# ConnectorHead_RPi.net
KiCad netlist of a schematic drawn in EAGLE
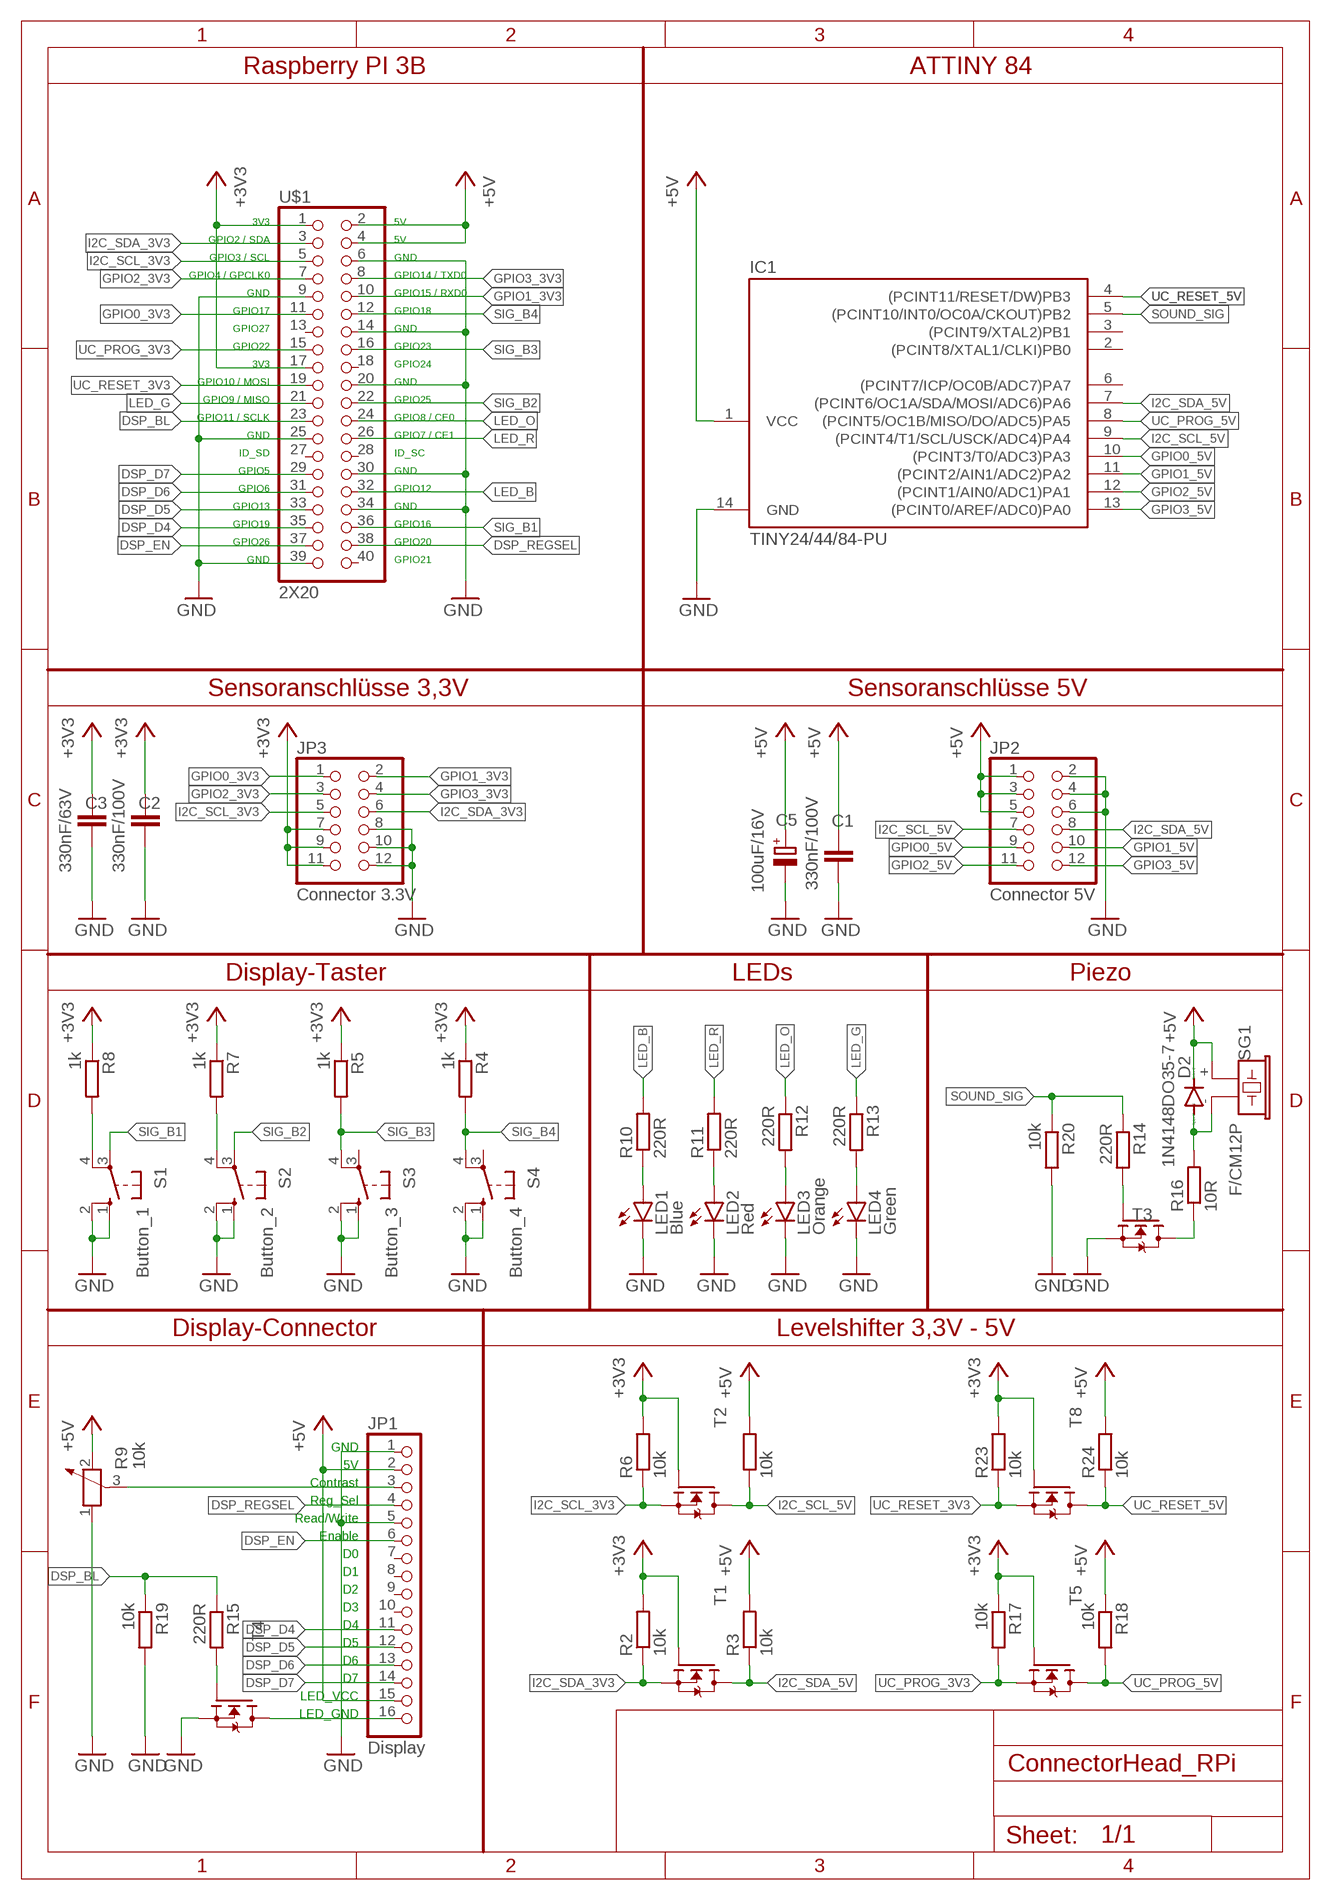
[diagram p0: schematic, sheet 1]

(export (version "E")
  (design (tool "Eeschema 10.0.6"))
  (components
    (comp (ref "C1")
      (value "330nF/100V")
      (footprint "eagle-import:C075-042X103")
      (libsource (lib "eagle-import") (part "C-EU075-042X103"))
    )
    (comp (ref "C2")
      (value "330nF/100V")
      (footprint "eagle-import:C075-042X103")
      (libsource (lib "eagle-import") (part "C-EU075-042X103"))
    )
    (comp (ref "C3")
      (value "330nF/63V")
      (footprint "eagle-import:C050-035X075")
      (libsource (lib "eagle-import") (part "C-EU050-035X075"))
    )
    (comp (ref "C5")
      (value "100uF/16V")
      (footprint "eagle-import:E2,5-6_FLAT_DOWN")
      (libsource (lib "eagle-import") (part "CPOL-EUE2.5-6_FLAT_DOWN"))
    )
    (comp (ref "D2")
      (value "1N4148DO35-7")
      (footprint "eagle-import:DO35-7")
      (libsource (lib "eagle-import") (part "1N4148DO35-7"))
    )
    (comp (ref "IC1")
      (value "TINY24/44/84-PU")
      (footprint "eagle-import:DIL14")
      (libsource (lib "eagle-import") (part "TINY24/44/84-PU"))
    )
    (comp (ref "JP1")
      (value "Display")
      (footprint "eagle-import:1X16F")
      (libsource (lib "eagle-import") (part "PINHD-1X16F1X16F"))
    )
    (comp (ref "JP2")
      (value "Connector 5V")
      (footprint "eagle-import:2X06_90")
      (libsource (lib "eagle-import") (part "PINHD-2X6/90"))
    )
    (comp (ref "JP3")
      (value "Connector 3.3V")
      (footprint "eagle-import:2X06_90")
      (libsource (lib "eagle-import") (part "PINHD-2X6/90"))
    )
    (comp (ref "LED1")
      (value "Blue")
      (footprint "eagle-import:LED5MM")
      (libsource (lib "eagle-import") (part "LED5MM"))
    )
    (comp (ref "LED2")
      (value "Red")
      (footprint "eagle-import:LED5MM")
      (libsource (lib "eagle-import") (part "LED5MM"))
    )
    (comp (ref "LED3")
      (value "Orange")
      (footprint "eagle-import:LED5MM")
      (libsource (lib "eagle-import") (part "LED5MM"))
    )
    (comp (ref "LED4")
      (value "Green")
      (footprint "eagle-import:LED5MM")
      (libsource (lib "eagle-import") (part "LED5MM"))
    )
    (comp (ref "R1")
      (value "10k")
      (footprint "eagle-import:0309V")
      (libsource (lib "eagle-import") (part "R-EU_0309/V"))
    )
    (comp (ref "R2")
      (value "10k")
      (footprint "eagle-import:0309V")
      (libsource (lib "eagle-import") (part "R-EU_0309/V"))
    )
    (comp (ref "R3")
      (value "10k")
      (footprint "eagle-import:0309V")
      (libsource (lib "eagle-import") (part "R-EU_0309/V"))
    )
    (comp (ref "R4")
      (value "1k")
      (footprint "eagle-import:0309V")
      (libsource (lib "eagle-import") (part "R-EU_0309/V"))
    )
    (comp (ref "R5")
      (value "1k")
      (footprint "eagle-import:0309V")
      (libsource (lib "eagle-import") (part "R-EU_0309/V"))
    )
    (comp (ref "R6")
      (value "10k")
      (footprint "eagle-import:0309V")
      (libsource (lib "eagle-import") (part "R-EU_0309/V"))
    )
    (comp (ref "R7")
      (value "1k")
      (footprint "eagle-import:0309V")
      (libsource (lib "eagle-import") (part "R-EU_0309/V"))
    )
    (comp (ref "R8")
      (value "1k")
      (footprint "eagle-import:0309V")
      (libsource (lib "eagle-import") (part "R-EU_0309/V"))
    )
    (comp (ref "R9")
      (value "10k")
      (footprint "eagle-import:PT-10")
      (libsource (lib "eagle-import") (part "POTENTIOMETER_PT-10"))
    )
    (comp (ref "R10")
      (value "220R")
      (footprint "eagle-import:0309V")
      (libsource (lib "eagle-import") (part "R-EU_0309/V"))
    )
    (comp (ref "R11")
      (value "220R")
      (footprint "eagle-import:0309V")
      (libsource (lib "eagle-import") (part "R-EU_0309/V"))
    )
    (comp (ref "R12")
      (value "220R")
      (footprint "eagle-import:0309V")
      (libsource (lib "eagle-import") (part "R-EU_0309/V"))
    )
    (comp (ref "R13")
      (value "220R")
      (footprint "eagle-import:0309V")
      (libsource (lib "eagle-import") (part "R-EU_0309/V"))
    )
    (comp (ref "R14")
      (value "220R")
      (footprint "eagle-import:0309V")
      (libsource (lib "eagle-import") (part "R-EU_0309/V"))
    )
    (comp (ref "R15")
      (value "220R")
      (footprint "eagle-import:0309V")
      (libsource (lib "eagle-import") (part "R-EU_0309/V"))
    )
    (comp (ref "R16")
      (value "10R")
      (footprint "eagle-import:0309V")
      (libsource (lib "eagle-import") (part "R-EU_0309/V"))
    )
    (comp (ref "R17")
      (value "10k")
      (footprint "eagle-import:0309V")
      (libsource (lib "eagle-import") (part "R-EU_0309/V"))
    )
    (comp (ref "R18")
      (value "10k")
      (footprint "eagle-import:0309V")
      (libsource (lib "eagle-import") (part "R-EU_0309/V"))
    )
    (comp (ref "R19")
      (value "10k")
      (footprint "eagle-import:0309V")
      (libsource (lib "eagle-import") (part "R-EU_0309/V"))
    )
    (comp (ref "R20")
      (value "10k")
      (footprint "eagle-import:0309V")
      (libsource (lib "eagle-import") (part "R-EU_0309/V"))
    )
    (comp (ref "R23")
      (value "10k")
      (footprint "eagle-import:0309V")
      (libsource (lib "eagle-import") (part "R-EU_0309/V"))
    )
    (comp (ref "R24")
      (value "10k")
      (footprint "eagle-import:0309V")
      (libsource (lib "eagle-import") (part "R-EU_0309/V"))
    )
    (comp (ref "S1")
      (value "Button_1")
      (footprint "eagle-import:B3F-10XX")
      (fields (field (name "MPN") "B3F-1000"))
      (libsource (lib "eagle-import") (part "10-XX"))
    )
    (comp (ref "S2")
      (value "Button_2")
      (footprint "eagle-import:B3F-10XX")
      (fields (field (name "MPN") "B3F-1000"))
      (libsource (lib "eagle-import") (part "10-XX"))
    )
    (comp (ref "S3")
      (value "Button_3")
      (footprint "eagle-import:B3F-10XX")
      (fields (field (name "MPN") "B3F-1000"))
      (libsource (lib "eagle-import") (part "10-XX"))
    )
    (comp (ref "S4")
      (value "Button_4")
      (footprint "eagle-import:B3F-10XX")
      (fields (field (name "MPN") "B3F-1000"))
      (libsource (lib "eagle-import") (part "10-XX"))
    )
    (comp (ref "SG1")
      (value "F/CM12P")
      (footprint "eagle-import:F_CM12P")
      (libsource (lib "eagle-import") (part "F/CM12P"))
    )
    (comp (ref "T1")
      (value "2N7000")
      (footprint "eagle-import:TO92")
      (fields (field (name "MF") "STMicroelectronics"))
      (libsource (lib "eagle-import") (part "2N7000"))
    )
    (comp (ref "T2")
      (value "2N7000")
      (footprint "eagle-import:TO92")
      (fields (field (name "MF") "STMicroelectronics"))
      (libsource (lib "eagle-import") (part "2N7000"))
    )
    (comp (ref "T3")
      (value "2N7000")
      (footprint "eagle-import:TO92")
      (fields (field (name "MF") "STMicroelectronics"))
      (libsource (lib "eagle-import") (part "2N7000"))
    )
    (comp (ref "T4")
      (value "2N7000")
      (footprint "eagle-import:TO92")
      (fields (field (name "MF") "STMicroelectronics"))
      (libsource (lib "eagle-import") (part "2N7000"))
    )
    (comp (ref "T5")
      (value "2N7000")
      (footprint "eagle-import:TO92")
      (fields (field (name "MF") "STMicroelectronics"))
      (libsource (lib "eagle-import") (part "2N7000"))
    )
    (comp (ref "T8")
      (value "2N7000")
      (footprint "eagle-import:TO92")
      (fields (field (name "MF") "STMicroelectronics"))
      (libsource (lib "eagle-import") (part "2N7000"))
    )
    (comp (ref "U$1")
      (value "2X20")
      (footprint "eagle-import:2X20")
      (libsource (lib "eagle-import") (part "2X20"))
    )
  )
  (nets
    (net (code "1") (name "+3V3") (class "Default")
      (node (ref "C2") (pin "1") (pinfunction "1_1") (pintype "passive"))
      (node (ref "C3") (pin "1") (pinfunction "1_1") (pintype "passive"))
      (node (ref "JP3") (pin "11") (pinfunction "11_11") (pintype "passive"))
      (node (ref "JP3") (pin "7") (pinfunction "7_7") (pintype "passive"))
      (node (ref "JP3") (pin "9") (pinfunction "9_9") (pintype "passive"))
      (node (ref "R17") (pin "1") (pinfunction "1_1") (pintype "passive"))
      (node (ref "R2") (pin "2") (pinfunction "2_2") (pintype "passive"))
      (node (ref "R23") (pin "2") (pinfunction "2_2") (pintype "passive"))
      (node (ref "R4") (pin "1") (pinfunction "1_1") (pintype "passive"))
      (node (ref "R5") (pin "1") (pinfunction "1_1") (pintype "passive"))
      (node (ref "R6") (pin "2") (pinfunction "2_2") (pintype "passive"))
      (node (ref "R7") (pin "1") (pinfunction "1_1") (pintype "passive"))
      (node (ref "R8") (pin "1") (pinfunction "1_1") (pintype "passive"))
      (node (ref "T1") (pin "2") (pinfunction "G_2") (pintype "passive"))
      (node (ref "T2") (pin "2") (pinfunction "G_2") (pintype "passive"))
      (node (ref "T5") (pin "2") (pinfunction "G_2") (pintype "passive"))
      (node (ref "T8") (pin "2") (pinfunction "G_2") (pintype "passive"))
      (node (ref "U$1") (pin "1") (pinfunction "1_1") (pintype "passive"))
      (node (ref "U$1") (pin "17") (pinfunction "17_17") (pintype "passive"))
    )
    (net (code "2") (name "+5V") (class "Default")
      (node (ref "C1") (pin "1") (pinfunction "1_1") (pintype "passive"))
      (node (ref "C5") (pin "+") (pinfunction "+_+") (pintype "passive"))
      (node (ref "D2") (pin "C") (pinfunction "C_C") (pintype "passive"))
      (node (ref "IC1") (pin "1") (pinfunction "VCC_1") (pintype "power_in"))
      (node (ref "JP1") (pin "15") (pinfunction "15_15") (pintype "passive"))
      (node (ref "JP1") (pin "2") (pinfunction "2_2") (pintype "passive"))
      (node (ref "JP2") (pin "1") (pinfunction "1_1") (pintype "passive"))
      (node (ref "JP2") (pin "3") (pinfunction "3_3") (pintype "passive"))
      (node (ref "JP2") (pin "5") (pinfunction "5_5") (pintype "passive"))
      (node (ref "R1") (pin "2") (pinfunction "2_2") (pintype "passive"))
      (node (ref "R18") (pin "1") (pinfunction "1_1") (pintype "passive"))
      (node (ref "R24") (pin "2") (pinfunction "2_2") (pintype "passive"))
      (node (ref "R3") (pin "2") (pinfunction "2_2") (pintype "passive"))
      (node (ref "R9") (pin "2") (pinfunction "2_2") (pintype "passive"))
      (node (ref "SG1") (pin "+") (pinfunction "1_+") (pintype "passive"))
      (node (ref "U$1") (pin "2") (pinfunction "2_2") (pintype "passive"))
      (node (ref "U$1") (pin "4") (pinfunction "4_4") (pintype "passive"))
    )
    (net (code "3") (name "DSP_BL") (class "Default")
      (node (ref "R15") (pin "1") (pinfunction "1_1") (pintype "passive"))
      (node (ref "R19") (pin "1") (pinfunction "1_1") (pintype "passive"))
      (node (ref "U$1") (pin "23") (pinfunction "23_23") (pintype "passive"))
    )
    (net (code "4") (name "DSP_D4") (class "Default")
      (node (ref "JP1") (pin "11") (pinfunction "11_11") (pintype "passive"))
      (node (ref "U$1") (pin "35") (pinfunction "35_35") (pintype "passive"))
    )
    (net (code "5") (name "DSP_D5") (class "Default")
      (node (ref "JP1") (pin "12") (pinfunction "12_12") (pintype "passive"))
      (node (ref "U$1") (pin "33") (pinfunction "33_33") (pintype "passive"))
    )
    (net (code "6") (name "DSP_D6") (class "Default")
      (node (ref "JP1") (pin "13") (pinfunction "13_13") (pintype "passive"))
      (node (ref "U$1") (pin "31") (pinfunction "31_31") (pintype "passive"))
    )
    (net (code "7") (name "DSP_D7") (class "Default")
      (node (ref "JP1") (pin "14") (pinfunction "14_14") (pintype "passive"))
      (node (ref "U$1") (pin "29") (pinfunction "29_29") (pintype "passive"))
    )
    (net (code "8") (name "DSP_EN") (class "Default")
      (node (ref "JP1") (pin "6") (pinfunction "6_6") (pintype "passive"))
      (node (ref "U$1") (pin "37") (pinfunction "37_37") (pintype "passive"))
    )
    (net (code "9") (name "DSP_REGSEL") (class "Default")
      (node (ref "JP1") (pin "4") (pinfunction "4_4") (pintype "passive"))
      (node (ref "U$1") (pin "38") (pinfunction "38_38") (pintype "passive"))
    )
    (net (code "10") (name "GND") (class "Default")
      (node (ref "C1") (pin "2") (pinfunction "2_2") (pintype "passive"))
      (node (ref "C2") (pin "2") (pinfunction "2_2") (pintype "passive"))
      (node (ref "C3") (pin "2") (pinfunction "2_2") (pintype "passive"))
      (node (ref "C5") (pin "-") (pinfunction "-_-") (pintype "passive"))
      (node (ref "IC1") (pin "14") (pinfunction "GND_14") (pintype "power_in"))
      (node (ref "JP1") (pin "1") (pinfunction "1_1") (pintype "passive"))
      (node (ref "JP1") (pin "5") (pinfunction "5_5") (pintype "passive"))
      (node (ref "JP2") (pin "2") (pinfunction "2_2") (pintype "passive"))
      (node (ref "JP2") (pin "4") (pinfunction "4_4") (pintype "passive"))
      (node (ref "JP2") (pin "6") (pinfunction "6_6") (pintype "passive"))
      (node (ref "JP3") (pin "10") (pinfunction "10_10") (pintype "passive"))
      (node (ref "JP3") (pin "12") (pinfunction "12_12") (pintype "passive"))
      (node (ref "JP3") (pin "8") (pinfunction "8_8") (pintype "passive"))
      (node (ref "LED1") (pin "K") (pinfunction "C_K") (pintype "passive"))
      (node (ref "LED2") (pin "K") (pinfunction "C_K") (pintype "passive"))
      (node (ref "LED3") (pin "K") (pinfunction "C_K") (pintype "passive"))
      (node (ref "LED4") (pin "K") (pinfunction "C_K") (pintype "passive"))
      (node (ref "R19") (pin "2") (pinfunction "2_2") (pintype "passive"))
      (node (ref "R20") (pin "2") (pinfunction "2_2") (pintype "passive"))
      (node (ref "R9") (pin "1") (pinfunction "1_1") (pintype "passive"))
      (node (ref "S1") (pin "1") (pinfunction "S_1") (pintype "passive"))
      (node (ref "S1") (pin "2") (pinfunction "S1_2") (pintype "passive"))
      (node (ref "S2") (pin "1") (pinfunction "S_1") (pintype "passive"))
      (node (ref "S2") (pin "2") (pinfunction "S1_2") (pintype "passive"))
      (node (ref "S3") (pin "1") (pinfunction "S_1") (pintype "passive"))
      (node (ref "S3") (pin "2") (pinfunction "S1_2") (pintype "passive"))
      (node (ref "S4") (pin "1") (pinfunction "S_1") (pintype "passive"))
      (node (ref "S4") (pin "2") (pinfunction "S1_2") (pintype "passive"))
      (node (ref "T3") (pin "3") (pinfunction "S_3") (pintype "passive"))
      (node (ref "T4") (pin "3") (pinfunction "S_3") (pintype "passive"))
      (node (ref "U$1") (pin "14") (pinfunction "14_14") (pintype "passive"))
      (node (ref "U$1") (pin "20") (pinfunction "20_20") (pintype "passive"))
      (node (ref "U$1") (pin "25") (pinfunction "25_25") (pintype "passive"))
      (node (ref "U$1") (pin "30") (pinfunction "30_30") (pintype "passive"))
      (node (ref "U$1") (pin "34") (pinfunction "34_34") (pintype "passive"))
      (node (ref "U$1") (pin "39") (pinfunction "39_39") (pintype "passive"))
      (node (ref "U$1") (pin "6") (pinfunction "6_6") (pintype "passive"))
      (node (ref "U$1") (pin "9") (pinfunction "9_9") (pintype "passive"))
    )
    (net (code "11") (name "GPIO0_3V3") (class "Default")
      (node (ref "JP3") (pin "1") (pinfunction "1_1") (pintype "passive"))
      (node (ref "U$1") (pin "11") (pinfunction "11_11") (pintype "passive"))
    )
    (net (code "12") (name "GPIO0_5V") (class "Default")
      (node (ref "IC1") (pin "10") (pinfunction "(PCINT3/T0/ADC3)PA3_10") (pintype "bidirectional"))
      (node (ref "JP2") (pin "9") (pinfunction "9_9") (pintype "passive"))
    )
    (net (code "13") (name "GPIO1_3V3") (class "Default")
      (node (ref "JP3") (pin "2") (pinfunction "2_2") (pintype "passive"))
      (node (ref "U$1") (pin "10") (pinfunction "10_10") (pintype "passive"))
    )
    (net (code "14") (name "GPIO1_5V") (class "Default")
      (node (ref "IC1") (pin "11") (pinfunction "(PCINT2/AIN1/ADC2)PA2_11") (pintype "bidirectional"))
      (node (ref "JP2") (pin "10") (pinfunction "10_10") (pintype "passive"))
    )
    (net (code "15") (name "GPIO2_3V3") (class "Default")
      (node (ref "JP3") (pin "3") (pinfunction "3_3") (pintype "passive"))
      (node (ref "U$1") (pin "7") (pinfunction "7_7") (pintype "passive"))
    )
    (net (code "16") (name "GPIO2_5V") (class "Default")
      (node (ref "IC1") (pin "12") (pinfunction "(PCINT1/AIN0/ADC1)PA1_12") (pintype "bidirectional"))
      (node (ref "JP2") (pin "11") (pinfunction "11_11") (pintype "passive"))
    )
    (net (code "17") (name "GPIO3_3V3") (class "Default")
      (node (ref "JP3") (pin "4") (pinfunction "4_4") (pintype "passive"))
      (node (ref "U$1") (pin "8") (pinfunction "8_8") (pintype "passive"))
    )
    (net (code "18") (name "GPIO3_5V") (class "Default")
      (node (ref "IC1") (pin "13") (pinfunction "(PCINT0/AREF/ADC0)PA0_13") (pintype "bidirectional"))
      (node (ref "JP2") (pin "12") (pinfunction "12_12") (pintype "passive"))
    )
    (net (code "19") (name "I2C_SCL_3V3") (class "Default")
      (node (ref "JP3") (pin "5") (pinfunction "5_5") (pintype "passive"))
      (node (ref "R6") (pin "1") (pinfunction "1_1") (pintype "passive"))
      (node (ref "T2") (pin "3") (pinfunction "S_3") (pintype "passive"))
      (node (ref "U$1") (pin "5") (pinfunction "5_5") (pintype "passive"))
    )
    (net (code "20") (name "I2C_SCL_5V") (class "Default")
      (node (ref "IC1") (pin "9") (pinfunction "(PCINT4/T1/SCL/USCK/ADC4)PA4_9") (pintype "bidirectional"))
      (node (ref "JP2") (pin "7") (pinfunction "7_7") (pintype "passive"))
      (node (ref "R1") (pin "1") (pinfunction "1_1") (pintype "passive"))
      (node (ref "T2") (pin "1") (pinfunction "D_1") (pintype "passive"))
    )
    (net (code "21") (name "I2C_SDA_3V3") (class "Default")
      (node (ref "JP3") (pin "6") (pinfunction "6_6") (pintype "passive"))
      (node (ref "R2") (pin "1") (pinfunction "1_1") (pintype "passive"))
      (node (ref "T1") (pin "3") (pinfunction "S_3") (pintype "passive"))
      (node (ref "U$1") (pin "3") (pinfunction "3_3") (pintype "passive"))
    )
    (net (code "22") (name "I2C_SDA_5V") (class "Default")
      (node (ref "IC1") (pin "7") (pinfunction "(PCINT6/OC1A/SDA/MOSI/ADC6)PA6_7") (pintype "bidirectional"))
      (node (ref "JP2") (pin "8") (pinfunction "8_8") (pintype "passive"))
      (node (ref "R3") (pin "1") (pinfunction "1_1") (pintype "passive"))
      (node (ref "T1") (pin "1") (pinfunction "D_1") (pintype "passive"))
    )
    (net (code "23") (name "LED_B") (class "Default")
      (node (ref "R10") (pin "2") (pinfunction "2_2") (pintype "passive"))
      (node (ref "U$1") (pin "32") (pinfunction "32_32") (pintype "passive"))
    )
    (net (code "24") (name "LED_G") (class "Default")
      (node (ref "R13") (pin "1") (pinfunction "1_1") (pintype "passive"))
      (node (ref "U$1") (pin "21") (pinfunction "21_21") (pintype "passive"))
    )
    (net (code "25") (name "LED_O") (class "Default")
      (node (ref "R12") (pin "1") (pinfunction "1_1") (pintype "passive"))
      (node (ref "U$1") (pin "24") (pinfunction "24_24") (pintype "passive"))
    )
    (net (code "26") (name "LED_R") (class "Default")
      (node (ref "R11") (pin "2") (pinfunction "2_2") (pintype "passive"))
      (node (ref "U$1") (pin "26") (pinfunction "26_26") (pintype "passive"))
    )
    (net (code "27") (name "Net-(JP1-Pad3)") (class "Default")
      (node (ref "JP1") (pin "3") (pinfunction "3_3") (pintype "passive"))
      (node (ref "R9") (pin "3") (pinfunction "3_3") (pintype "passive"))
    )
    (net (code "28") (name "Net-(LED1-PadA)") (class "Default")
      (node (ref "LED1") (pin "A") (pinfunction "A_A") (pintype "passive"))
      (node (ref "R10") (pin "1") (pinfunction "1_1") (pintype "passive"))
    )
    (net (code "29") (name "Net-(LED2-PadA)") (class "Default")
      (node (ref "LED2") (pin "A") (pinfunction "A_A") (pintype "passive"))
      (node (ref "R11") (pin "1") (pinfunction "1_1") (pintype "passive"))
    )
    (net (code "30") (name "Net-(LED3-PadA)") (class "Default")
      (node (ref "LED3") (pin "A") (pinfunction "A_A") (pintype "passive"))
      (node (ref "R12") (pin "2") (pinfunction "2_2") (pintype "passive"))
    )
    (net (code "31") (name "Net-(LED4-PadA)") (class "Default")
      (node (ref "LED4") (pin "A") (pinfunction "A_A") (pintype "passive"))
      (node (ref "R13") (pin "2") (pinfunction "2_2") (pintype "passive"))
    )
    (net (code "32") (name "Net-(S1-P1)") (class "Default")
      (node (ref "R8") (pin "2") (pinfunction "2_2") (pintype "passive"))
      (node (ref "S1") (pin "4") (pinfunction "P1_4") (pintype "passive"))
    )
    (net (code "33") (name "Net-(S2-P1)") (class "Default")
      (node (ref "R7") (pin "2") (pinfunction "2_2") (pintype "passive"))
      (node (ref "S2") (pin "4") (pinfunction "P1_4") (pintype "passive"))
    )
    (net (code "34") (name "Net-(SG1-2)") (class "Default")
      (node (ref "D2") (pin "A") (pinfunction "A_A") (pintype "passive"))
      (node (ref "R16") (pin "2") (pinfunction "2_2") (pintype "passive"))
      (node (ref "SG1") (pin "-") (pinfunction "2_-") (pintype "passive"))
    )
    (net (code "35") (name "Net-(T3-D)") (class "Default")
      (node (ref "R16") (pin "1") (pinfunction "1_1") (pintype "passive"))
      (node (ref "T3") (pin "1") (pinfunction "D_1") (pintype "passive"))
    )
    (net (code "36") (name "Net-(T3-G)") (class "Default")
      (node (ref "R14") (pin "2") (pinfunction "2_2") (pintype "passive"))
      (node (ref "T3") (pin "2") (pinfunction "G_2") (pintype "passive"))
    )
    (net (code "37") (name "Net-(T4-D)") (class "Default")
      (node (ref "JP1") (pin "16") (pinfunction "16_16") (pintype "passive"))
      (node (ref "T4") (pin "1") (pinfunction "D_1") (pintype "passive"))
    )
    (net (code "38") (name "Net-(T4-G)") (class "Default")
      (node (ref "R15") (pin "2") (pinfunction "2_2") (pintype "passive"))
      (node (ref "T4") (pin "2") (pinfunction "G_2") (pintype "passive"))
    )
    (net (code "39") (name "SIG_B1") (class "Default")
      (node (ref "S1") (pin "3") (pinfunction "P_3") (pintype "passive"))
      (node (ref "U$1") (pin "36") (pinfunction "36_36") (pintype "passive"))
    )
    (net (code "40") (name "SIG_B2") (class "Default")
      (node (ref "S2") (pin "3") (pinfunction "P_3") (pintype "passive"))
      (node (ref "U$1") (pin "22") (pinfunction "22_22") (pintype "passive"))
    )
    (net (code "41") (name "SIG_B3") (class "Default")
      (node (ref "R5") (pin "2") (pinfunction "2_2") (pintype "passive"))
      (node (ref "S3") (pin "4") (pinfunction "P1_4") (pintype "passive"))
      (node (ref "U$1") (pin "16") (pinfunction "16_16") (pintype "passive"))
    )
    (net (code "42") (name "SIG_B4") (class "Default")
      (node (ref "R4") (pin "2") (pinfunction "2_2") (pintype "passive"))
      (node (ref "S4") (pin "4") (pinfunction "P1_4") (pintype "passive"))
      (node (ref "U$1") (pin "12") (pinfunction "12_12") (pintype "passive"))
    )
    (net (code "43") (name "SOUND_SIG") (class "Default")
      (node (ref "IC1") (pin "5") (pinfunction "(PCINT10/INT0/OC0A/CKOUT)PB2_5") (pintype "bidirectional"))
      (node (ref "R14") (pin "1") (pinfunction "1_1") (pintype "passive"))
      (node (ref "R20") (pin "1") (pinfunction "1_1") (pintype "passive"))
    )
    (net (code "44") (name "UC_PROG_3V3") (class "Default")
      (node (ref "R17") (pin "2") (pinfunction "2_2") (pintype "passive"))
      (node (ref "T5") (pin "3") (pinfunction "S_3") (pintype "passive"))
      (node (ref "U$1") (pin "15") (pinfunction "15_15") (pintype "passive"))
    )
    (net (code "45") (name "UC_PROG_5V") (class "Default")
      (node (ref "IC1") (pin "8") (pinfunction "(PCINT5/OC1B/MISO/DO/ADC5)PA5_8") (pintype "bidirectional"))
      (node (ref "R18") (pin "2") (pinfunction "2_2") (pintype "passive"))
      (node (ref "T5") (pin "1") (pinfunction "D_1") (pintype "passive"))
    )
    (net (code "46") (name "UC_RESET_3V3") (class "Default")
      (node (ref "R23") (pin "1") (pinfunction "1_1") (pintype "passive"))
      (node (ref "T8") (pin "3") (pinfunction "S_3") (pintype "passive"))
      (node (ref "U$1") (pin "19") (pinfunction "19_19") (pintype "passive"))
    )
    (net (code "47") (name "UC_RESET_5V") (class "Default")
      (node (ref "IC1") (pin "4") (pinfunction "(PCINT11/RESET/DW)PB3_4") (pintype "bidirectional"))
      (node (ref "R24") (pin "1") (pinfunction "1_1") (pintype "passive"))
      (node (ref "T8") (pin "1") (pinfunction "D_1") (pintype "passive"))
    )
    (net (code "48") (name "unconnected-(IC1-(PCINT7{slash}ICP{slash}OC0B{slash}ADC7)PA7-Pad6)") (class "Default")
      (node (ref "IC1") (pin "6") (pinfunction "(PCINT7/ICP/OC0B/ADC7)PA7_6") (pintype "bidirectional"))
    )
    (net (code "49") (name "unconnected-(IC1-(PCINT8{slash}XTAL1{slash}CLKI)PB0-Pad2)") (class "Default")
      (node (ref "IC1") (pin "2") (pinfunction "(PCINT8/XTAL1/CLKI)PB0_2") (pintype "bidirectional"))
    )
    (net (code "50") (name "unconnected-(IC1-(PCINT9{slash}XTAL2)PB1-Pad3)") (class "Default")
      (node (ref "IC1") (pin "3") (pinfunction "(PCINT9/XTAL2)PB1_3") (pintype "bidirectional"))
    )
    (net (code "51") (name "unconnected-(JP1-Pad7)") (class "Default")
      (node (ref "JP1") (pin "7") (pinfunction "7_7") (pintype "passive"))
    )
    (net (code "52") (name "unconnected-(JP1-Pad8)") (class "Default")
      (node (ref "JP1") (pin "8") (pinfunction "8_8") (pintype "passive"))
    )
    (net (code "53") (name "unconnected-(JP1-Pad9)") (class "Default")
      (node (ref "JP1") (pin "9") (pinfunction "9_9") (pintype "passive"))
    )
    (net (code "54") (name "unconnected-(JP1-Pad10)") (class "Default")
      (node (ref "JP1") (pin "10") (pinfunction "10_10") (pintype "passive"))
    )
    (net (code "55") (name "unconnected-(S3-P-Pad3)") (class "Default")
      (node (ref "S3") (pin "3") (pinfunction "P_3") (pintype "passive"))
    )
    (net (code "56") (name "unconnected-(S4-P-Pad3)") (class "Default")
      (node (ref "S4") (pin "3") (pinfunction "P_3") (pintype "passive"))
    )
    (net (code "57") (name "unconnected-(U$1-Pad13)") (class "Default")
      (node (ref "U$1") (pin "13") (pinfunction "13_13") (pintype "passive"))
    )
    (net (code "58") (name "unconnected-(U$1-Pad18)") (class "Default")
      (node (ref "U$1") (pin "18") (pinfunction "18_18") (pintype "passive"))
    )
    (net (code "59") (name "unconnected-(U$1-Pad27)") (class "Default")
      (node (ref "U$1") (pin "27") (pinfunction "27_27") (pintype "passive"))
    )
    (net (code "60") (name "unconnected-(U$1-Pad28)") (class "Default")
      (node (ref "U$1") (pin "28") (pinfunction "28_28") (pintype "passive"))
    )
    (net (code "61") (name "unconnected-(U$1-Pad40)") (class "Default")
      (node (ref "U$1") (pin "40") (pinfunction "40_40") (pintype "passive"))
    )
  )
)
